# Ulimate.net
KiCad netlist of a schematic drawn in EAGLE
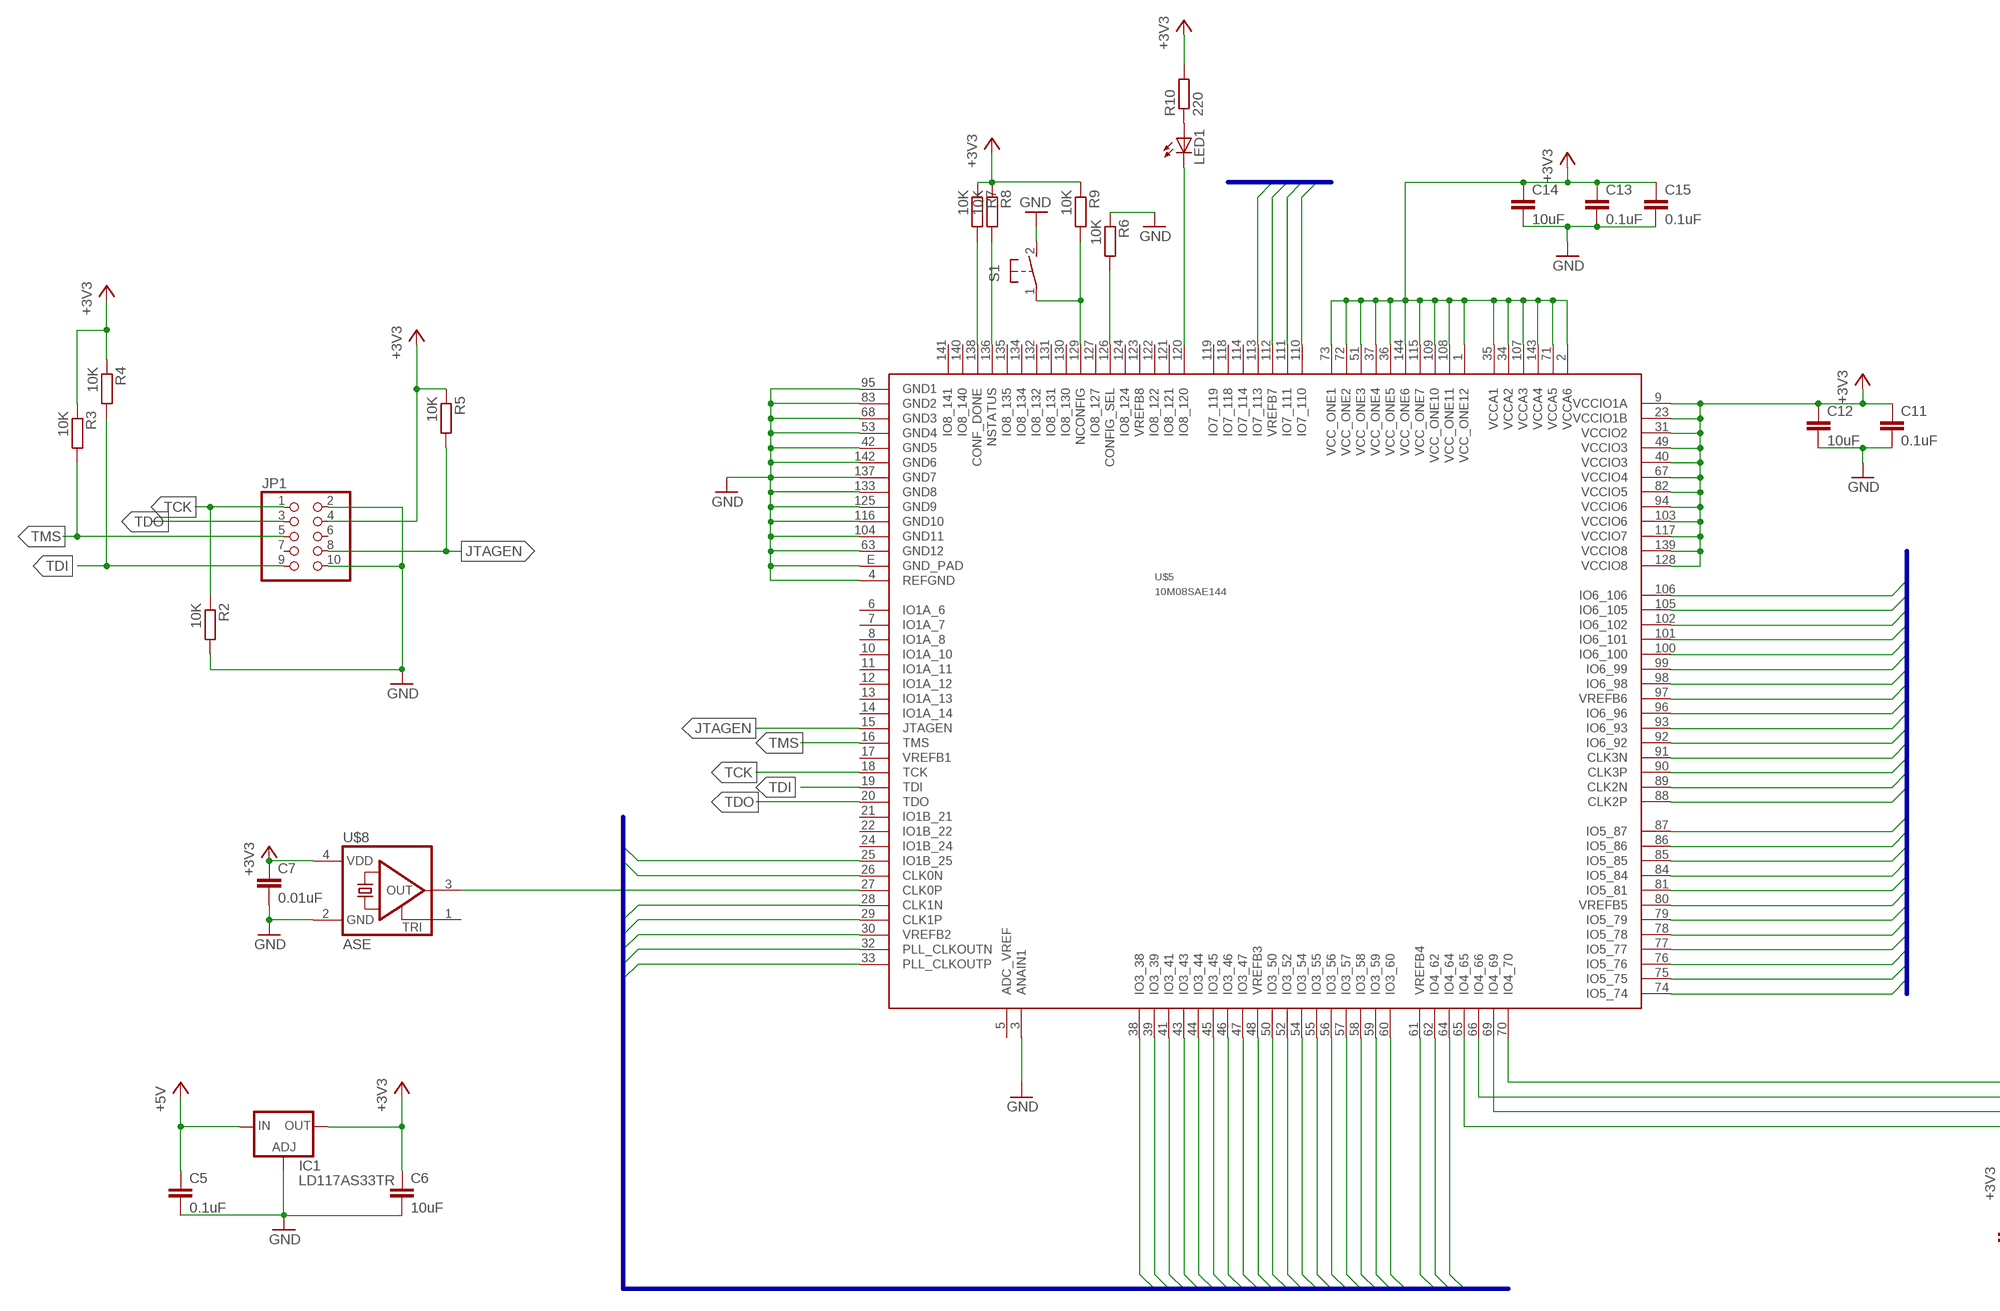
[diagram p0: schematic, sheet 1, part 1 of 2]
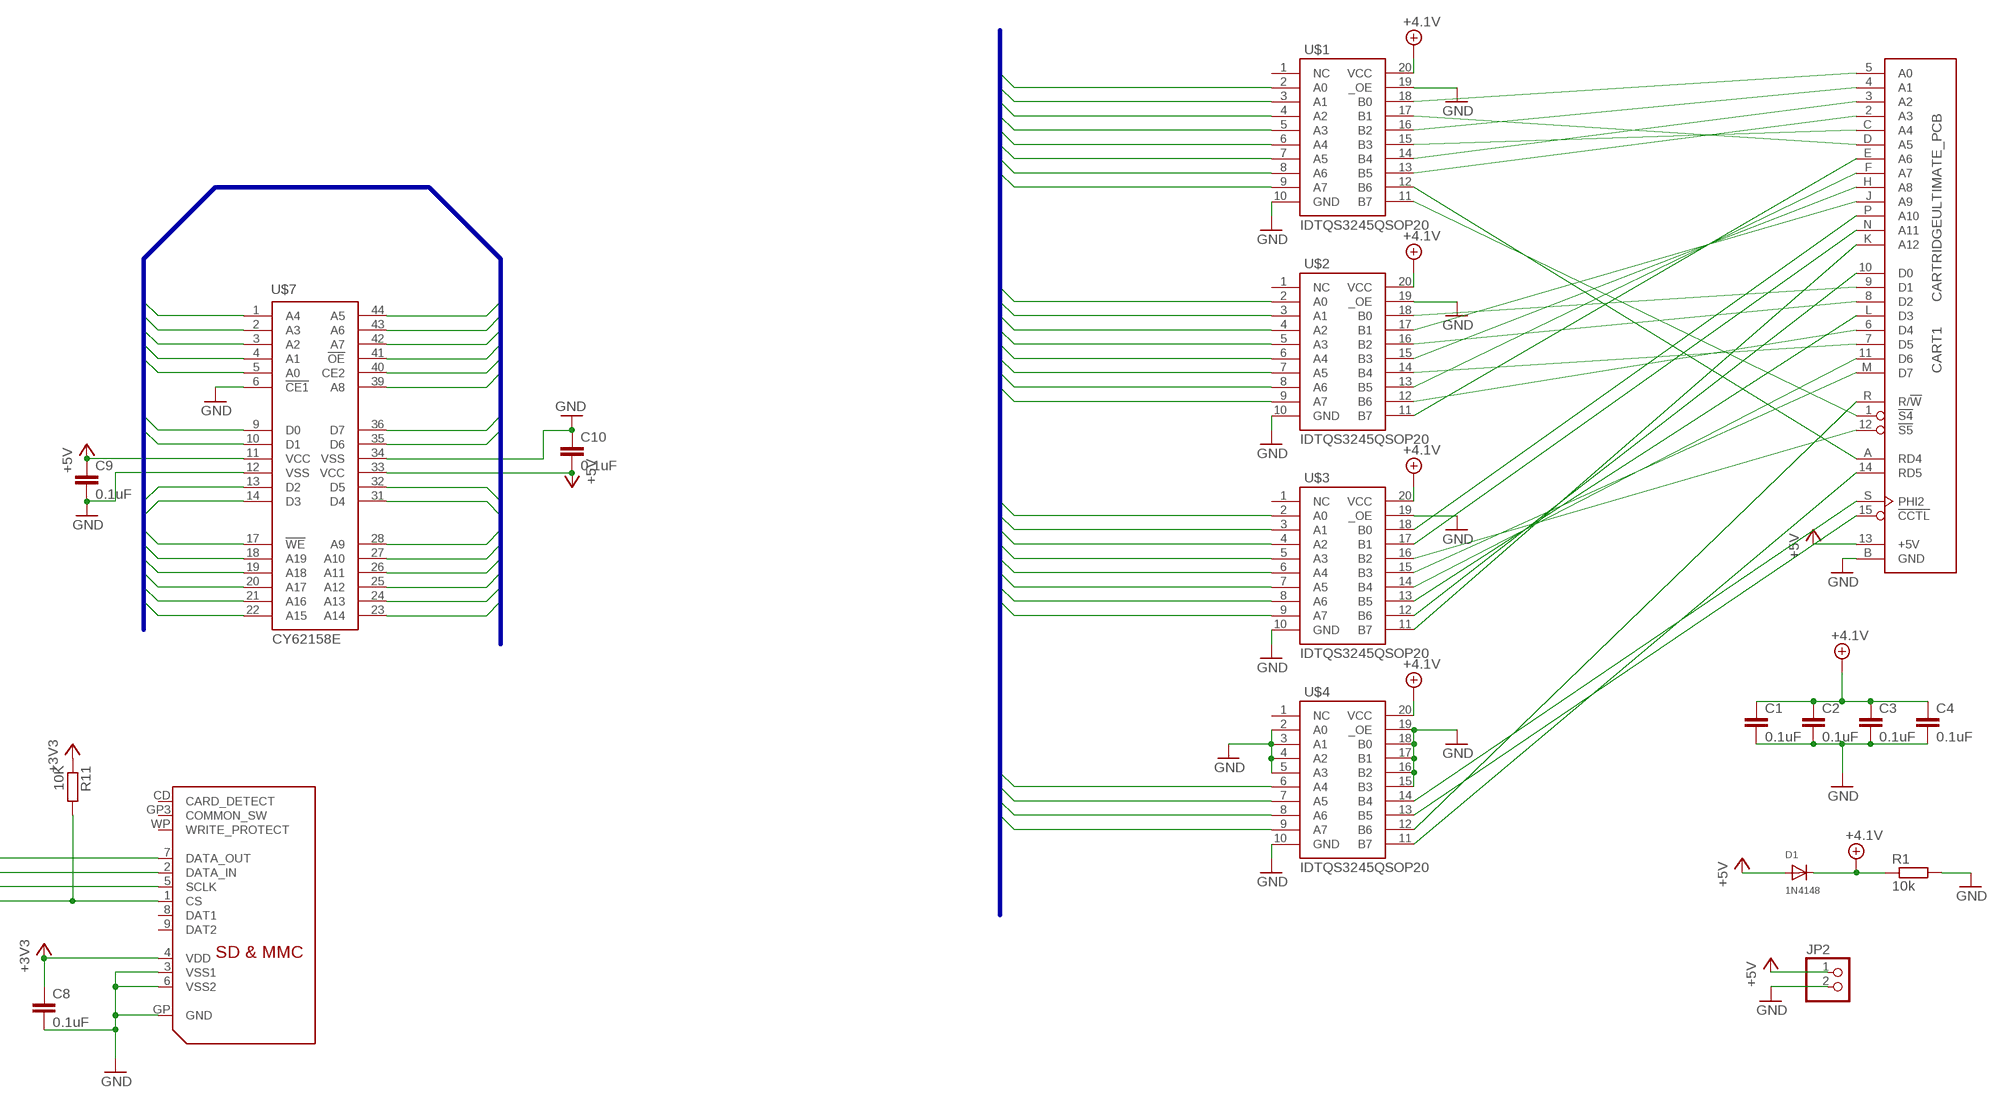
[diagram p1: schematic, sheet 1, part 2 of 2]

(export (version "E")
  (design (tool "Eeschema 10.0.6"))
  (components
    (comp (ref "C1")
      (value "0.1uF")
      (footprint "eagle-import:C0805K")
      (libsource (lib "eagle-import") (part "C-EUC0805K"))
    )
    (comp (ref "C2")
      (value "0.1uF")
      (footprint "eagle-import:C0805K")
      (libsource (lib "eagle-import") (part "C-EUC0805K"))
    )
    (comp (ref "C3")
      (value "0.1uF")
      (footprint "eagle-import:C0805K")
      (libsource (lib "eagle-import") (part "C-EUC0805K"))
    )
    (comp (ref "C4")
      (value "0.1uF")
      (footprint "eagle-import:C0805K")
      (libsource (lib "eagle-import") (part "C-EUC0805K"))
    )
    (comp (ref "C5")
      (value "0.1uF")
      (footprint "eagle-import:C0805K")
      (libsource (lib "eagle-import") (part "C-EUC0805K"))
    )
    (comp (ref "C6")
      (value "10uF")
      (footprint "eagle-import:C0805K")
      (libsource (lib "eagle-import") (part "C-EUC0805K"))
    )
    (comp (ref "C7")
      (value "0.01uF")
      (footprint "eagle-import:C0805K")
      (libsource (lib "eagle-import") (part "C-EUC0805K"))
    )
    (comp (ref "C8")
      (value "0.1uF")
      (footprint "eagle-import:C0805K")
      (libsource (lib "eagle-import") (part "C-EUC0805K"))
    )
    (comp (ref "C9")
      (value "0.1uF")
      (footprint "eagle-import:C0805K")
      (libsource (lib "eagle-import") (part "C-EUC0805K"))
    )
    (comp (ref "C10")
      (value "0.1uF")
      (footprint "eagle-import:C0805K")
      (libsource (lib "eagle-import") (part "C-EUC0805K"))
    )
    (comp (ref "C11")
      (value "0.1uF")
      (footprint "eagle-import:C0805K")
      (libsource (lib "eagle-import") (part "C-EUC0805K"))
    )
    (comp (ref "C12")
      (value "10uF")
      (footprint "eagle-import:C0805K")
      (libsource (lib "eagle-import") (part "C-EUC0805K"))
    )
    (comp (ref "C13")
      (value "0.1uF")
      (footprint "eagle-import:C0805K")
      (libsource (lib "eagle-import") (part "C-EUC0805K"))
    )
    (comp (ref "C14")
      (value "10uF")
      (footprint "eagle-import:C0805K")
      (libsource (lib "eagle-import") (part "C-EUC0805K"))
    )
    (comp (ref "C15")
      (value "0.1uF")
      (footprint "eagle-import:C0805K")
      (libsource (lib "eagle-import") (part "C-EUC0805K"))
    )
    (comp (ref "CART1")
      (value "CARTRIDGEULTIMATE_PCB")
      (footprint "eagle-import:CART_ULTIMATE")
      (libsource (lib "eagle-import") (part "CARTRIDGEULTIMATE_PCB"))
    )
    (comp (ref "D1")
      (value "1N4148")
      (footprint "eagle-import:SOD-123FL")
      (libsource (lib "eagle-import") (part "DIODE_SOD-123FL"))
    )
    (comp (ref "IC1")
      (value "LD117AS33TR")
      (footprint "eagle-import:SOT223")
      (libsource (lib "eagle-import") (part "LD117A?S33TR"))
    )
    (comp (ref "JP1")
      (value "PINHD-2X5")
      (footprint "eagle-import:2X05")
      (libsource (lib "eagle-import") (part "PINHD-2X5"))
    )
    (comp (ref "JP2")
      (value "PINHD-1X2")
      (footprint "eagle-import:1X02")
      (libsource (lib "eagle-import") (part "PINHD-1X2"))
    )
    (comp (ref "LED1")
      (value "LEDSML0805")
      (footprint "eagle-import:SML0805")
      (libsource (lib "eagle-import") (part "LEDSML0805"))
    )
    (comp (ref "R1")
      (value "10k")
      (footprint "eagle-import:R0805")
      (libsource (lib "eagle-import") (part "R-EU_R0805"))
    )
    (comp (ref "R2")
      (value "10K")
      (footprint "eagle-import:R0805")
      (libsource (lib "eagle-import") (part "R-EU_R0805"))
    )
    (comp (ref "R3")
      (value "10K")
      (footprint "eagle-import:R0805")
      (libsource (lib "eagle-import") (part "R-EU_R0805"))
    )
    (comp (ref "R4")
      (value "10K")
      (footprint "eagle-import:R0805")
      (libsource (lib "eagle-import") (part "R-EU_R0805"))
    )
    (comp (ref "R5")
      (value "10K")
      (footprint "eagle-import:R0805")
      (libsource (lib "eagle-import") (part "R-EU_R0805"))
    )
    (comp (ref "R6")
      (value "10K")
      (footprint "eagle-import:R0805")
      (libsource (lib "eagle-import") (part "R-EU_R0805"))
    )
    (comp (ref "R7")
      (value "10K")
      (footprint "eagle-import:R0805")
      (libsource (lib "eagle-import") (part "R-EU_R0805"))
    )
    (comp (ref "R8")
      (value "10K")
      (footprint "eagle-import:R0805")
      (libsource (lib "eagle-import") (part "R-EU_R0805"))
    )
    (comp (ref "R9")
      (value "10K")
      (footprint "eagle-import:R0805")
      (libsource (lib "eagle-import") (part "R-EU_R0805"))
    )
    (comp (ref "R10")
      (value "220")
      (footprint "eagle-import:R0805")
      (libsource (lib "eagle-import") (part "R-EU_R0805"))
    )
    (comp (ref "R11")
      (value "10K")
      (footprint "eagle-import:R0805")
      (libsource (lib "eagle-import") (part "R-EU_R0805"))
    )
    (comp (ref "S1")
      (value "31-XXSKINNY")
      (footprint "eagle-import:B3F-31XX-SKINNIER")
      (libsource (lib "eagle-import") (part "31-XXSKINNY"))
    )
    (comp (ref "U$1")
      (value "IDTQS3245QSOP20")
      (footprint "eagle-import:QSOP20")
      (libsource (lib "eagle-import") (part "IDTQS3245QSOP20"))
    )
    (comp (ref "U$2")
      (value "IDTQS3245QSOP20")
      (footprint "eagle-import:QSOP20")
      (libsource (lib "eagle-import") (part "IDTQS3245QSOP20"))
    )
    (comp (ref "U$3")
      (value "IDTQS3245QSOP20")
      (footprint "eagle-import:QSOP20")
      (libsource (lib "eagle-import") (part "IDTQS3245QSOP20"))
    )
    (comp (ref "U$4")
      (value "IDTQS3245QSOP20")
      (footprint "eagle-import:QSOP20")
      (libsource (lib "eagle-import") (part "IDTQS3245QSOP20"))
    )
    (comp (ref "U$5")
      (value "10M08SAE144")
      (footprint "eagle-import:EQFP144")
      (libsource (lib "eagle-import") (part "10M08SAE144"))
    )
    (comp (ref "U$6")
      (value "SDMMC06132")
      (footprint "eagle-import:06132")
      (libsource (lib "eagle-import") (part "SDMMC06132"))
    )
    (comp (ref "U$7")
      (value "CY62158E")
      (footprint "eagle-import:TSOP44-II")
      (libsource (lib "eagle-import") (part "CY62158E"))
    )
    (comp (ref "U$8")
      (value "ASE")
      (footprint "eagle-import:ASE")
      (libsource (lib "eagle-import") (part "ASE"))
    )
  )
  (nets
    (net (code "1") (name "+3V3") (class "Default")
      (node (ref "C11") (pin "1") (pinfunction "1_1") (pintype "passive"))
      (node (ref "C12") (pin "1") (pinfunction "1_1") (pintype "passive"))
      (node (ref "C13") (pin "1") (pinfunction "1_1") (pintype "passive"))
      (node (ref "C14") (pin "1") (pinfunction "1_1") (pintype "passive"))
      (node (ref "C15") (pin "1") (pinfunction "1_1") (pintype "passive"))
      (node (ref "C6") (pin "1") (pinfunction "1_1") (pintype "passive"))
      (node (ref "C7") (pin "1") (pinfunction "1_1") (pintype "passive"))
      (node (ref "C8") (pin "1") (pinfunction "1_1") (pintype "passive"))
      (node (ref "IC1") (pin "4") (pinfunction "OUT_4") (pintype "passive"))
      (node (ref "JP1") (pin "4") (pinfunction "4_4") (pintype "passive"))
      (node (ref "R10") (pin "2") (pinfunction "2_2") (pintype "passive"))
      (node (ref "R11") (pin "1") (pinfunction "1_1") (pintype "passive"))
      (node (ref "R3") (pin "1") (pinfunction "1_1") (pintype "passive"))
      (node (ref "R4") (pin "1") (pinfunction "1_1") (pintype "passive"))
      (node (ref "R5") (pin "1") (pinfunction "1_1") (pintype "passive"))
      (node (ref "R7") (pin "1") (pinfunction "1_1") (pintype "passive"))
      (node (ref "R8") (pin "1") (pinfunction "1_1") (pintype "passive"))
      (node (ref "R9") (pin "1") (pinfunction "1_1") (pintype "passive"))
      (node (ref "U$5") (pin "1") (pinfunction "VCC_ONE12_1") (pintype "bidirectional"))
      (node (ref "U$5") (pin "103") (pinfunction "VCCIO6_103") (pintype "bidirectional"))
      (node (ref "U$5") (pin "107") (pinfunction "VCCA3_107") (pintype "bidirectional"))
      (node (ref "U$5") (pin "108") (pinfunction "VCC_ONE11_108") (pintype "bidirectional"))
      (node (ref "U$5") (pin "109") (pinfunction "VCC_ONE10_109") (pintype "bidirectional"))
      (node (ref "U$5") (pin "115") (pinfunction "VCC_ONE7_115") (pintype "bidirectional"))
      (node (ref "U$5") (pin "117") (pinfunction "VCCIO7_117") (pintype "bidirectional"))
      (node (ref "U$5") (pin "128") (pinfunction "VCCIO8_128") (pintype "bidirectional"))
      (node (ref "U$5") (pin "139") (pinfunction "VCCIO8_139") (pintype "bidirectional"))
      (node (ref "U$5") (pin "143") (pinfunction "VCCA4_143") (pintype "bidirectional"))
      (node (ref "U$5") (pin "144") (pinfunction "VCC_ONE6_144") (pintype "bidirectional"))
      (node (ref "U$5") (pin "2") (pinfunction "VCCA6_2") (pintype "bidirectional"))
      (node (ref "U$5") (pin "23") (pinfunction "VCCIO1B_23") (pintype "bidirectional"))
      (node (ref "U$5") (pin "31") (pinfunction "VCCIO2_31") (pintype "bidirectional"))
      (node (ref "U$5") (pin "34") (pinfunction "VCCA2_34") (pintype "bidirectional"))
      (node (ref "U$5") (pin "35") (pinfunction "VCCA1_35") (pintype "bidirectional"))
      (node (ref "U$5") (pin "36") (pinfunction "VCC_ONE5_36") (pintype "bidirectional"))
      (node (ref "U$5") (pin "37") (pinfunction "VCC_ONE4_37") (pintype "bidirectional"))
      (node (ref "U$5") (pin "40") (pinfunction "VCCIO3_40") (pintype "bidirectional"))
      (node (ref "U$5") (pin "49") (pinfunction "VCCIO3_49") (pintype "bidirectional"))
      (node (ref "U$5") (pin "51") (pinfunction "VCC_ONE3_51") (pintype "bidirectional"))
      (node (ref "U$5") (pin "67") (pinfunction "VCCIO4_67") (pintype "bidirectional"))
      (node (ref "U$5") (pin "71") (pinfunction "VCCA5_71") (pintype "bidirectional"))
      (node (ref "U$5") (pin "72") (pinfunction "VCC_ONE2_72") (pintype "bidirectional"))
      (node (ref "U$5") (pin "73") (pinfunction "VCC_ONE1_73") (pintype "bidirectional"))
      (node (ref "U$5") (pin "82") (pinfunction "VCCIO5_82") (pintype "bidirectional"))
      (node (ref "U$5") (pin "9") (pinfunction "VCCIO1A_9") (pintype "bidirectional"))
      (node (ref "U$5") (pin "94") (pinfunction "VCCIO6_94") (pintype "bidirectional"))
      (node (ref "U$6") (pin "4") (pinfunction "VDD_4") (pintype "power_in"))
      (node (ref "U$8") (pin "4") (pinfunction "VDD_4") (pintype "power_in"))
    )
    (net (code "2") (name "+4.1V") (class "Default")
      (node (ref "C1") (pin "1") (pinfunction "1_1") (pintype "passive"))
      (node (ref "C2") (pin "1") (pinfunction "1_1") (pintype "passive"))
      (node (ref "C3") (pin "1") (pinfunction "1_1") (pintype "passive"))
      (node (ref "C4") (pin "1") (pinfunction "1_1") (pintype "passive"))
      (node (ref "D1") (pin "C") (pinfunction "C_C") (pintype "passive"))
      (node (ref "R1") (pin "1") (pinfunction "1_1") (pintype "passive"))
      (node (ref "U$1") (pin "20") (pinfunction "VCC_20") (pintype "power_in"))
      (node (ref "U$2") (pin "20") (pinfunction "VCC_20") (pintype "power_in"))
      (node (ref "U$3") (pin "20") (pinfunction "VCC_20") (pintype "power_in"))
      (node (ref "U$4") (pin "20") (pinfunction "VCC_20") (pintype "power_in"))
    )
    (net (code "3") (name "+5V") (class "Default")
      (node (ref "C10") (pin "2") (pinfunction "2_2") (pintype "passive"))
      (node (ref "C5") (pin "1") (pinfunction "1_1") (pintype "passive"))
      (node (ref "C9") (pin "1") (pinfunction "1_1") (pintype "passive"))
      (node (ref "CART1") (pin "13") (pinfunction "+5V_13") (pintype "power_in"))
      (node (ref "D1") (pin "A") (pinfunction "A_A") (pintype "passive"))
      (node (ref "IC1") (pin "3") (pinfunction "IN_3") (pintype "input"))
      (node (ref "JP2") (pin "1") (pinfunction "1_1") (pintype "passive"))
      (node (ref "U$7") (pin "11") (pinfunction "VCC_11") (pintype "bidirectional"))
      (node (ref "U$7") (pin "33") (pinfunction "VCC_33") (pintype "bidirectional"))
    )
    (net (code "4") (name "/A0") (class "Default")
      (node (ref "U$5") (pin "96") (pinfunction "IO6_96_96") (pintype "bidirectional"))
      (node (ref "U$7") (pin "5") (pinfunction "A0_5") (pintype "bidirectional"))
    )
    (net (code "5") (name "/A1") (class "Default")
      (node (ref "U$5") (pin "97") (pinfunction "VREFB6_97") (pintype "bidirectional"))
      (node (ref "U$7") (pin "4") (pinfunction "A1_4") (pintype "bidirectional"))
    )
    (net (code "6") (name "/A2") (class "Default")
      (node (ref "U$5") (pin "98") (pinfunction "IO6_98_98") (pintype "bidirectional"))
      (node (ref "U$7") (pin "3") (pinfunction "A2_3") (pintype "bidirectional"))
    )
    (net (code "7") (name "/A3") (class "Default")
      (node (ref "U$5") (pin "99") (pinfunction "IO6_99_99") (pintype "bidirectional"))
      (node (ref "U$7") (pin "2") (pinfunction "A3_2") (pintype "bidirectional"))
    )
    (net (code "8") (name "/A4") (class "Default")
      (node (ref "U$5") (pin "100") (pinfunction "IO6_100_100") (pintype "bidirectional"))
      (node (ref "U$7") (pin "1") (pinfunction "A4_1") (pintype "bidirectional"))
    )
    (net (code "9") (name "/A5") (class "Default")
      (node (ref "U$5") (pin "105") (pinfunction "IO6_105_105") (pintype "bidirectional"))
      (node (ref "U$7") (pin "44") (pinfunction "A5_44") (pintype "bidirectional"))
    )
    (net (code "10") (name "/A6") (class "Default")
      (node (ref "U$5") (pin "102") (pinfunction "IO6_102_102") (pintype "bidirectional"))
      (node (ref "U$7") (pin "43") (pinfunction "A6_43") (pintype "bidirectional"))
    )
    (net (code "11") (name "/A7") (class "Default")
      (node (ref "U$5") (pin "101") (pinfunction "IO6_101_101") (pintype "bidirectional"))
      (node (ref "U$7") (pin "42") (pinfunction "A7_42") (pintype "bidirectional"))
    )
    (net (code "12") (name "/A8") (class "Default")
      (node (ref "U$5") (pin "111") (pinfunction "IO7_111_111") (pintype "bidirectional"))
      (node (ref "U$7") (pin "39") (pinfunction "A8_39") (pintype "bidirectional"))
    )
    (net (code "13") (name "/A9") (class "Default")
      (node (ref "U$5") (pin "76") (pinfunction "IO5_76_76") (pintype "bidirectional"))
      (node (ref "U$7") (pin "28") (pinfunction "A9_28") (pintype "bidirectional"))
    )
    (net (code "14") (name "/A10") (class "Default")
      (node (ref "U$5") (pin "77") (pinfunction "IO5_77_77") (pintype "bidirectional"))
      (node (ref "U$7") (pin "27") (pinfunction "A10_27") (pintype "bidirectional"))
    )
    (net (code "15") (name "/A11") (class "Default")
      (node (ref "U$5") (pin "78") (pinfunction "IO5_78_78") (pintype "bidirectional"))
      (node (ref "U$7") (pin "26") (pinfunction "A11_26") (pintype "bidirectional"))
    )
    (net (code "16") (name "/A12") (class "Default")
      (node (ref "U$5") (pin "79") (pinfunction "IO5_79_79") (pintype "bidirectional"))
      (node (ref "U$7") (pin "25") (pinfunction "A12_25") (pintype "bidirectional"))
    )
    (net (code "17") (name "/A13") (class "Default")
      (node (ref "U$5") (pin "80") (pinfunction "VREFB5_80") (pintype "bidirectional"))
      (node (ref "U$7") (pin "24") (pinfunction "A13_24") (pintype "bidirectional"))
    )
    (net (code "18") (name "/A14") (class "Default")
      (node (ref "U$5") (pin "81") (pinfunction "IO5_81_81") (pintype "bidirectional"))
      (node (ref "U$7") (pin "23") (pinfunction "A14_23") (pintype "bidirectional"))
    )
    (net (code "19") (name "/A15") (class "Default")
      (node (ref "U$5") (pin "84") (pinfunction "IO5_84_84") (pintype "bidirectional"))
      (node (ref "U$7") (pin "22") (pinfunction "A15_22") (pintype "bidirectional"))
    )
    (net (code "20") (name "/A16") (class "Default")
      (node (ref "U$5") (pin "85") (pinfunction "IO5_85_85") (pintype "bidirectional"))
      (node (ref "U$7") (pin "21") (pinfunction "A16_21") (pintype "bidirectional"))
    )
    (net (code "21") (name "/A17") (class "Default")
      (node (ref "U$5") (pin "86") (pinfunction "IO5_86_86") (pintype "bidirectional"))
      (node (ref "U$7") (pin "20") (pinfunction "A17_20") (pintype "bidirectional"))
    )
    (net (code "22") (name "/A18") (class "Default")
      (node (ref "U$5") (pin "87") (pinfunction "IO5_87_87") (pintype "bidirectional"))
      (node (ref "U$7") (pin "19") (pinfunction "A18_19") (pintype "bidirectional"))
    )
    (net (code "23") (name "/A19") (class "Default")
      (node (ref "U$5") (pin "88") (pinfunction "CLK2P_88") (pintype "bidirectional"))
      (node (ref "U$7") (pin "18") (pinfunction "A19_18") (pintype "bidirectional"))
    )
    (net (code "24") (name "/CART_A0") (class "Default")
      (node (ref "U$1") (pin "2") (pinfunction "A0_2") (pintype "bidirectional"))
      (node (ref "U$5") (pin "39") (pinfunction "IO3_39_39") (pintype "bidirectional"))
    )
    (net (code "25") (name "/CART_A1") (class "Default")
      (node (ref "U$1") (pin "4") (pinfunction "A2_4") (pintype "bidirectional"))
      (node (ref "U$5") (pin "33") (pinfunction "PLL_CLKOUTP_33") (pintype "bidirectional"))
    )
    (net (code "26") (name "/CART_A2") (class "Default")
      (node (ref "U$1") (pin "6") (pinfunction "A4_6") (pintype "bidirectional"))
      (node (ref "U$5") (pin "30") (pinfunction "VREFB2_30") (pintype "bidirectional"))
    )
    (net (code "27") (name "/CART_A3") (class "Default")
      (node (ref "U$1") (pin "7") (pinfunction "A5_7") (pintype "bidirectional"))
      (node (ref "U$5") (pin "29") (pinfunction "CLK1P_29") (pintype "bidirectional"))
    )
    (net (code "28") (name "/CART_A4") (class "Default")
      (node (ref "U$1") (pin "5") (pinfunction "A3_5") (pintype "bidirectional"))
      (node (ref "U$5") (pin "32") (pinfunction "PLL_CLKOUTN_32") (pintype "bidirectional"))
    )
    (net (code "29") (name "/CART_A5") (class "Default")
      (node (ref "U$1") (pin "3") (pinfunction "A1_3") (pintype "bidirectional"))
      (node (ref "U$5") (pin "38") (pinfunction "IO3_38_38") (pintype "bidirectional"))
    )
    (net (code "30") (name "/CART_A6") (class "Default")
      (node (ref "U$2") (pin "9") (pinfunction "A7_9") (pintype "bidirectional"))
      (node (ref "U$5") (pin "41") (pinfunction "IO3_41_41") (pintype "bidirectional"))
    )
    (net (code "31") (name "/CART_A7") (class "Default")
      (node (ref "U$2") (pin "7") (pinfunction "A5_7") (pintype "bidirectional"))
      (node (ref "U$5") (pin "44") (pinfunction "IO3_44_44") (pintype "bidirectional"))
    )
    (net (code "32") (name "/CART_A8") (class "Default")
      (node (ref "U$2") (pin "5") (pinfunction "A3_5") (pintype "bidirectional"))
      (node (ref "U$5") (pin "46") (pinfunction "IO3_46_46") (pintype "bidirectional"))
    )
    (net (code "33") (name "/CART_A9") (class "Default")
      (node (ref "U$2") (pin "3") (pinfunction "A1_3") (pintype "bidirectional"))
      (node (ref "U$5") (pin "48") (pinfunction "VREFB3_48") (pintype "bidirectional"))
    )
    (net (code "34") (name "/CART_A10") (class "Default")
      (node (ref "U$3") (pin "2") (pinfunction "A0_2") (pintype "bidirectional"))
      (node (ref "U$5") (pin "60") (pinfunction "IO3_60_60") (pintype "bidirectional"))
    )
    (net (code "35") (name "/CART_A11") (class "Default")
      (node (ref "U$3") (pin "3") (pinfunction "A1_3") (pintype "bidirectional"))
      (node (ref "U$5") (pin "59") (pinfunction "IO3_59_59") (pintype "bidirectional"))
    )
    (net (code "36") (name "/CART_A12") (class "Default")
      (node (ref "U$3") (pin "9") (pinfunction "A7_9") (pintype "bidirectional"))
      (node (ref "U$5") (pin "52") (pinfunction "IO3_52_52") (pintype "bidirectional"))
    )
    (net (code "37") (name "/CART_CTL") (class "Default")
      (node (ref "U$4") (pin "7") (pinfunction "A5_7") (pintype "bidirectional"))
      (node (ref "U$5") (pin "64") (pinfunction "IO4_64_64") (pintype "bidirectional"))
    )
    (net (code "38") (name "/CART_D0") (class "Default")
      (node (ref "U$3") (pin "8") (pinfunction "A6_8") (pintype "bidirectional"))
      (node (ref "U$5") (pin "54") (pinfunction "IO3_54_54") (pintype "bidirectional"))
    )
    (net (code "39") (name "/CART_D1") (class "Default")
      (node (ref "U$2") (pin "2") (pinfunction "A0_2") (pintype "bidirectional"))
      (node (ref "U$5") (pin "50") (pinfunction "IO3_50_50") (pintype "bidirectional"))
    )
    (net (code "40") (name "/CART_D2") (class "Default")
      (node (ref "U$2") (pin "4") (pinfunction "A2_4") (pintype "bidirectional"))
      (node (ref "U$5") (pin "47") (pinfunction "IO3_47_47") (pintype "bidirectional"))
    )
    (net (code "41") (name "/CART_D3") (class "Default")
      (node (ref "U$3") (pin "7") (pinfunction "A5_7") (pintype "bidirectional"))
      (node (ref "U$5") (pin "55") (pinfunction "IO3_55_55") (pintype "bidirectional"))
    )
    (net (code "42") (name "/CART_D4") (class "Default")
      (node (ref "U$2") (pin "8") (pinfunction "A6_8") (pintype "bidirectional"))
      (node (ref "U$5") (pin "43") (pinfunction "IO3_43_43") (pintype "bidirectional"))
    )
    (net (code "43") (name "/CART_D5") (class "Default")
      (node (ref "U$2") (pin "6") (pinfunction "A4_6") (pintype "bidirectional"))
      (node (ref "U$5") (pin "45") (pinfunction "IO3_45_45") (pintype "bidirectional"))
    )
    (net (code "44") (name "/CART_D6") (class "Default")
      (node (ref "U$3") (pin "6") (pinfunction "A4_6") (pintype "bidirectional"))
      (node (ref "U$5") (pin "56") (pinfunction "IO3_56_56") (pintype "bidirectional"))
    )
    (net (code "45") (name "/CART_D7") (class "Default")
      (node (ref "U$3") (pin "5") (pinfunction "A3_5") (pintype "bidirectional"))
      (node (ref "U$5") (pin "57") (pinfunction "IO3_57_57") (pintype "bidirectional"))
    )
    (net (code "46") (name "/CART_PHI") (class "Default")
      (node (ref "U$4") (pin "6") (pinfunction "A4_6") (pintype "bidirectional"))
      (node (ref "U$5") (pin "26") (pinfunction "CLK0N_26") (pintype "bidirectional"))
    )
    (net (code "47") (name "/CART_RD4") (class "Default")
      (node (ref "U$1") (pin "8") (pinfunction "A6_8") (pintype "bidirectional"))
      (node (ref "U$5") (pin "25") (pinfunction "IO1B_25_25") (pintype "bidirectional"))
    )
    (net (code "48") (name "/CART_RD5") (class "Default")
      (node (ref "U$4") (pin "9") (pinfunction "A7_9") (pintype "bidirectional"))
      (node (ref "U$5") (pin "61") (pinfunction "VREFB4_61") (pintype "bidirectional"))
    )
    (net (code "49") (name "/CART_RW") (class "Default")
      (node (ref "U$4") (pin "8") (pinfunction "A6_8") (pintype "bidirectional"))
      (node (ref "U$5") (pin "62") (pinfunction "IO4_62_62") (pintype "bidirectional"))
    )
    (net (code "50") (name "/CART_S4") (class "Default")
      (node (ref "U$1") (pin "9") (pinfunction "A7_9") (pintype "bidirectional"))
      (node (ref "U$5") (pin "28") (pinfunction "CLK1N_28") (pintype "bidirectional"))
    )
    (net (code "51") (name "/CART_S5") (class "Default")
      (node (ref "U$3") (pin "4") (pinfunction "A2_4") (pintype "bidirectional"))
      (node (ref "U$5") (pin "58") (pinfunction "IO3_58_58") (pintype "bidirectional"))
    )
    (net (code "52") (name "/CE") (class "Default")
      (node (ref "U$5") (pin "110") (pinfunction "IO7_110_110") (pintype "bidirectional"))
      (node (ref "U$7") (pin "40") (pinfunction "CE2_40") (pintype "bidirectional"))
    )
    (net (code "53") (name "/D0") (class "Default")
      (node (ref "U$5") (pin "93") (pinfunction "IO6_93_93") (pintype "bidirectional"))
      (node (ref "U$7") (pin "9") (pinfunction "D0_9") (pintype "bidirectional"))
    )
    (net (code "54") (name "/D1") (class "Default")
      (node (ref "U$5") (pin "92") (pinfunction "IO6_92_92") (pintype "bidirectional"))
      (node (ref "U$7") (pin "10") (pinfunction "D1_10") (pintype "bidirectional"))
    )
    (net (code "55") (name "/D2") (class "Default")
      (node (ref "U$5") (pin "91") (pinfunction "CLK3N_91") (pintype "bidirectional"))
      (node (ref "U$7") (pin "13") (pinfunction "D2_13") (pintype "bidirectional"))
    )
    (net (code "56") (name "/D3") (class "Default")
      (node (ref "U$5") (pin "90") (pinfunction "CLK3P_90") (pintype "bidirectional"))
      (node (ref "U$7") (pin "14") (pinfunction "D3_14") (pintype "bidirectional"))
    )
    (net (code "57") (name "/D4") (class "Default")
      (node (ref "U$5") (pin "75") (pinfunction "IO5_75_75") (pintype "bidirectional"))
      (node (ref "U$7") (pin "31") (pinfunction "D4_31") (pintype "bidirectional"))
    )
    (net (code "58") (name "/D5") (class "Default")
      (node (ref "U$5") (pin "74") (pinfunction "IO5_74_74") (pintype "bidirectional"))
      (node (ref "U$7") (pin "32") (pinfunction "D5_32") (pintype "bidirectional"))
    )
    (net (code "59") (name "/D6") (class "Default")
      (node (ref "U$5") (pin "113") (pinfunction "IO7_113_113") (pintype "bidirectional"))
      (node (ref "U$7") (pin "35") (pinfunction "D6_35") (pintype "bidirectional"))
    )
    (net (code "60") (name "/D7") (class "Default")
      (node (ref "U$5") (pin "112") (pinfunction "VREFB7_112") (pintype "bidirectional"))
      (node (ref "U$7") (pin "36") (pinfunction "D7_36") (pintype "bidirectional"))
    )
    (net (code "63") (name "/~{OE}") (class "Default")
      (node (ref "U$5") (pin "106") (pinfunction "IO6_106_106") (pintype "bidirectional"))
      (node (ref "U$7") (pin "41") (pinfunction "~{OE}_41") (pintype "bidirectional"))
    )
    (net (code "64") (name "/~{WE}") (class "Default")
      (node (ref "U$5") (pin "89") (pinfunction "CLK2N_89") (pintype "bidirectional"))
      (node (ref "U$7") (pin "17") (pinfunction "~{WE}_17") (pintype "bidirectional"))
    )
    (net (code "65") (name "GND") (class "Default")
      (node (ref "C1") (pin "2") (pinfunction "2_2") (pintype "passive"))
      (node (ref "C10") (pin "1") (pinfunction "1_1") (pintype "passive"))
      (node (ref "C11") (pin "2") (pinfunction "2_2") (pintype "passive"))
      (node (ref "C12") (pin "2") (pinfunction "2_2") (pintype "passive"))
      (node (ref "C13") (pin "2") (pinfunction "2_2") (pintype "passive"))
      (node (ref "C14") (pin "2") (pinfunction "2_2") (pintype "passive"))
      (node (ref "C15") (pin "2") (pinfunction "2_2") (pintype "passive"))
      (node (ref "C2") (pin "2") (pinfunction "2_2") (pintype "passive"))
      (node (ref "C3") (pin "2") (pinfunction "2_2") (pintype "passive"))
      (node (ref "C4") (pin "2") (pinfunction "2_2") (pintype "passive"))
      (node (ref "C5") (pin "2") (pinfunction "2_2") (pintype "passive"))
      (node (ref "C6") (pin "2") (pinfunction "2_2") (pintype "passive"))
      (node (ref "C7") (pin "2") (pinfunction "2_2") (pintype "passive"))
      (node (ref "C8") (pin "2") (pinfunction "2_2") (pintype "passive"))
      (node (ref "C9") (pin "2") (pinfunction "2_2") (pintype "passive"))
      (node (ref "CART1") (pin "B") (pinfunction "GND_B") (pintype "power_in"))
      (node (ref "IC1") (pin "1") (pinfunction "ADJ_1") (pintype "input"))
      (node (ref "JP1") (pin "10") (pinfunction "10_10") (pintype "passive"))
      (node (ref "JP1") (pin "2") (pinfunction "2_2") (pintype "passive"))
      (node (ref "JP2") (pin "2") (pinfunction "2_2") (pintype "passive"))
      (node (ref "R1") (pin "2") (pinfunction "2_2") (pintype "passive"))
      (node (ref "R2") (pin "2") (pinfunction "2_2") (pintype "passive"))
      (node (ref "R6") (pin "1") (pinfunction "1_1") (pintype "passive"))
      (node (ref "S1") (pin "2") (pinfunction "S_2") (pintype "passive"))
      (node (ref "U$1") (pin "10") (pinfunction "GND_10") (pintype "power_in"))
      (node (ref "U$1") (pin "19") (pinfunction "_OE_19") (pintype "bidirectional"))
      (node (ref "U$2") (pin "10") (pinfunction "GND_10") (pintype "power_in"))
      (node (ref "U$2") (pin "19") (pinfunction "_OE_19") (pintype "bidirectional"))
      (node (ref "U$3") (pin "10") (pinfunction "GND_10") (pintype "power_in"))
      (node (ref "U$3") (pin "19") (pinfunction "_OE_19") (pintype "bidirectional"))
      (node (ref "U$4") (pin "10") (pinfunction "GND_10") (pintype "power_in"))
      (node (ref "U$4") (pin "15") (pinfunction "B3_15") (pintype "bidirectional"))
      (node (ref "U$4") (pin "16") (pinfunction "B2_16") (pintype "bidirectional"))
      (node (ref "U$4") (pin "17") (pinfunction "B1_17") (pintype "bidirectional"))
      (node (ref "U$4") (pin "18") (pinfunction "B0_18") (pintype "bidirectional"))
      (node (ref "U$4") (pin "19") (pinfunction "_OE_19") (pintype "bidirectional"))
      (node (ref "U$4") (pin "2") (pinfunction "A0_2") (pintype "bidirectional"))
      (node (ref "U$4") (pin "3") (pinfunction "A1_3") (pintype "bidirectional"))
      (node (ref "U$4") (pin "4") (pinfunction "A2_4") (pintype "bidirectional"))
      (node (ref "U$4") (pin "5") (pinfunction "A3_5") (pintype "bidirectional"))
      (node (ref "U$5") (pin "104") (pinfunction "GND11_104") (pintype "bidirectional"))
      (node (ref "U$5") (pin "116") (pinfunction "GND10_116") (pintype "bidirectional"))
      (node (ref "U$5") (pin "125") (pinfunction "GND9_125") (pintype "bidirectional"))
      (node (ref "U$5") (pin "133") (pinfunction "GND8_133") (pintype "bidirectional"))
      (node (ref "U$5") (pin "137") (pinfunction "GND7_137") (pintype "bidirectional"))
      (node (ref "U$5") (pin "142") (pinfunction "GND6_142") (pintype "bidirectional"))
      (node (ref "U$5") (pin "3") (pinfunction "ANAIN1_3") (pintype "bidirectional"))
      (node (ref "U$5") (pin "4") (pinfunction "REFGND_4") (pintype "bidirectional"))
      (node (ref "U$5") (pin "42") (pinfunction "GND5_42") (pintype "bidirectional"))
      (node (ref "U$5") (pin "53") (pinfunction "GND4_53") (pintype "bidirectional"))
      (node (ref "U$5") (pin "63") (pinfunction "GND12_63") (pintype "bidirectional"))
      (node (ref "U$5") (pin "68") (pinfunction "GND3_68") (pintype "bidirectional"))
      (node (ref "U$5") (pin "83") (pinfunction "GND2_83") (pintype "bidirectional"))
      (node (ref "U$5") (pin "95") (pinfunction "GND1_95") (pintype "bidirectional"))
      (node (ref "U$5") (pin "E") (pinfunction "GND_PAD_E") (pintype "bidirectional"))
      (node (ref "U$6") (pin "3") (pinfunction "VSS1_3") (pintype "power_in"))
      (node (ref "U$6") (pin "6") (pinfunction "VSS2_6") (pintype "power_in"))
      (node (ref "U$6") (pin "GP") (pinfunction "GND_GP") (pintype "power_in"))
      (node (ref "U$7") (pin "12") (pinfunction "VSS_12") (pintype "bidirectional"))
      (node (ref "U$7") (pin "34") (pinfunction "VSS_34") (pintype "bidirectional"))
      (node (ref "U$7") (pin "6") (pinfunction "~{CE1}_6") (pintype "bidirectional"))
      (node (ref "U$8") (pin "2") (pinfunction "GND_2") (pintype "power_in"))
    )
    (net (code "66") (name "JTAGEN") (class "Default")
      (node (ref "JP1") (pin "8") (pinfunction "8_8") (pintype "passive"))
      (node (ref "R5") (pin "2") (pinfunction "2_2") (pintype "passive"))
      (node (ref "U$5") (pin "15") (pinfunction "JTAGEN_15") (pintype "bidirectional"))
    )
    (net (code "67") (name "Net-(CART1-A0)") (class "Default")
      (node (ref "CART1") (pin "5") (pinfunction "A0_5") (pintype "output"))
      (node (ref "U$1") (pin "18") (pinfunction "B0_18") (pintype "bidirectional"))
    )
    (net (code "68") (name "Net-(CART1-A1)") (class "Default")
      (node (ref "CART1") (pin "4") (pinfunction "A1_4") (pintype "output"))
      (node (ref "U$1") (pin "16") (pinfunction "B2_16") (pintype "bidirectional"))
    )
    (net (code "69") (name "Net-(CART1-A2)") (class "Default")
      (node (ref "CART1") (pin "3") (pinfunction "A2_3") (pintype "output"))
      (node (ref "U$1") (pin "14") (pinfunction "B4_14") (pintype "bidirectional"))
    )
    (net (code "70") (name "Net-(CART1-A3)") (class "Default")
      (node (ref "CART1") (pin "2") (pinfunction "A3_2") (pintype "output"))
      (node (ref "U$1") (pin "13") (pinfunction "B5_13") (pintype "bidirectional"))
    )
    (net (code "71") (name "Net-(CART1-A4)") (class "Default")
      (node (ref "CART1") (pin "C") (pinfunction "A4_C") (pintype "output"))
      (node (ref "U$1") (pin "15") (pinfunction "B3_15") (pintype "bidirectional"))
    )
    (net (code "72") (name "Net-(CART1-A5)") (class "Default")
      (node (ref "CART1") (pin "D") (pinfunction "A5_D") (pintype "output"))
      (node (ref "U$1") (pin "17") (pinfunction "B1_17") (pintype "bidirectional"))
    )
    (net (code "73") (name "Net-(CART1-A6)") (class "Default")
      (node (ref "CART1") (pin "E") (pinfunction "A6_E") (pintype "output"))
      (node (ref "U$2") (pin "11") (pinfunction "B7_11") (pintype "bidirectional"))
    )
    (net (code "74") (name "Net-(CART1-A7)") (class "Default")
      (node (ref "CART1") (pin "F") (pinfunction "A7_F") (pintype "output"))
      (node (ref "U$2") (pin "13") (pinfunction "B5_13") (pintype "bidirectional"))
    )
    (net (code "75") (name "Net-(CART1-A8)") (class "Default")
      (node (ref "CART1") (pin "H") (pinfunction "A8_H") (pintype "output"))
      (node (ref "U$2") (pin "15") (pinfunction "B3_15") (pintype "bidirectional"))
    )
    (net (code "76") (name "Net-(CART1-A9)") (class "Default")
      (node (ref "CART1") (pin "J") (pinfunction "A9_J") (pintype "output"))
      (node (ref "U$2") (pin "17") (pinfunction "B1_17") (pintype "bidirectional"))
    )
    (net (code "77") (name "Net-(CART1-A10)") (class "Default")
      (node (ref "CART1") (pin "P") (pinfunction "A10_P") (pintype "output"))
      (node (ref "U$3") (pin "18") (pinfunction "B0_18") (pintype "bidirectional"))
    )
    (net (code "78") (name "Net-(CART1-A11)") (class "Default")
      (node (ref "CART1") (pin "N") (pinfunction "A11_N") (pintype "output"))
      (node (ref "U$3") (pin "17") (pinfunction "B1_17") (pintype "bidirectional"))
    )
    (net (code "79") (name "Net-(CART1-A12)") (class "Default")
      (node (ref "CART1") (pin "K") (pinfunction "A12_K") (pintype "output"))
      (node (ref "U$3") (pin "11") (pinfunction "B7_11") (pintype "bidirectional"))
    )
    (net (code "80") (name "Net-(CART1-D0)") (class "Default")
      (node (ref "CART1") (pin "10") (pinfunction "D0_10") (pintype "bidirectional"))
      (node (ref "U$3") (pin "12") (pinfunction "B6_12") (pintype "bidirectional"))
    )
    (net (code "81") (name "Net-(CART1-D1)") (class "Default")
      (node (ref "CART1") (pin "9") (pinfunction "D1_9") (pintype "bidirectional"))
      (node (ref "U$2") (pin "18") (pinfunction "B0_18") (pintype "bidirectional"))
    )
    (net (code "82") (name "Net-(CART1-D2)") (class "Default")
      (node (ref "CART1") (pin "8") (pinfunction "D2_8") (pintype "bidirectional"))
      (node (ref "U$2") (pin "16") (pinfunction "B2_16") (pintype "bidirectional"))
    )
    (net (code "83") (name "Net-(CART1-D3)") (class "Default")
      (node (ref "CART1") (pin "L") (pinfunction "D3_L") (pintype "bidirectional"))
      (node (ref "U$3") (pin "13") (pinfunction "B5_13") (pintype "bidirectional"))
    )
    (net (code "84") (name "Net-(CART1-D4)") (class "Default")
      (node (ref "CART1") (pin "6") (pinfunction "D4_6") (pintype "bidirectional"))
      (node (ref "U$2") (pin "12") (pinfunction "B6_12") (pintype "bidirectional"))
    )
    (net (code "85") (name "Net-(CART1-D5)") (class "Default")
      (node (ref "CART1") (pin "7") (pinfunction "D5_7") (pintype "bidirectional"))
      (node (ref "U$2") (pin "14") (pinfunction "B4_14") (pintype "bidirectional"))
    )
    (net (code "86") (name "Net-(CART1-D6)") (class "Default")
      (node (ref "CART1") (pin "11") (pinfunction "D6_11") (pintype "bidirectional"))
      (node (ref "U$3") (pin "14") (pinfunction "B4_14") (pintype "bidirectional"))
    )
    (net (code "87") (name "Net-(CART1-D7)") (class "Default")
      (node (ref "CART1") (pin "M") (pinfunction "D7_M") (pintype "bidirectional"))
      (node (ref "U$3") (pin "15") (pinfunction "B3_15") (pintype "bidirectional"))
    )
    (net (code "88") (name "Net-(CART1-PHI2)") (class "Default")
      (node (ref "CART1") (pin "S") (pinfunction "PHI2_S") (pintype "output"))
      (node (ref "U$4") (pin "14") (pinfunction "B4_14") (pintype "bidirectional"))
    )
    (net (code "89") (name "Net-(CART1-RD4)") (class "Default")
      (node (ref "CART1") (pin "A") (pinfunction "RD4_A") (pintype "input"))
      (node (ref "U$1") (pin "12") (pinfunction "B6_12") (pintype "bidirectional"))
    )
    (net (code "90") (name "Net-(CART1-RD5)") (class "Default")
      (node (ref "CART1") (pin "14") (pinfunction "RD5_14") (pintype "input"))
      (node (ref "U$4") (pin "11") (pinfunction "B7_11") (pintype "bidirectional"))
    )
    (net (code "91") (name "Net-(CART1-R{slash}~{W})") (class "Default")
      (node (ref "CART1") (pin "R") (pinfunction "R/~{W}_R") (pintype "output"))
      (node (ref "U$4") (pin "12") (pinfunction "B6_12") (pintype "bidirectional"))
    )
    (net (code "92") (name "Net-(CART1-~{CCTL})") (class "Default")
      (node (ref "CART1") (pin "15") (pinfunction "~{CCTL}_15") (pintype "output"))
      (node (ref "U$4") (pin "13") (pinfunction "B5_13") (pintype "bidirectional"))
    )
    (net (code "93") (name "Net-(CART1-~{S4})") (class "Default")
      (node (ref "CART1") (pin "1") (pinfunction "~{S4}_1") (pintype "output"))
      (node (ref "U$1") (pin "11") (pinfunction "B7_11") (pintype "bidirectional"))
    )
    (net (code "94") (name "Net-(CART1-~{S5})") (class "Default")
      (node (ref "CART1") (pin "12") (pinfunction "~{S5}_12") (pintype "output"))
      (node (ref "U$3") (pin "16") (pinfunction "B2_16") (pintype "bidirectional"))
    )
    (net (code "95") (name "Net-(LED1-PadA)") (class "Default")
      (node (ref "LED1") (pin "A") (pinfunction "A_A") (pintype "passive"))
      (node (ref "R10") (pin "1") (pinfunction "1_1") (pintype "passive"))
    )
    (net (code "96") (name "Net-(S1-P)") (class "Default")
      (node (ref "R9") (pin "2") (pinfunction "2_2") (pintype "passive"))
      (node (ref "S1") (pin "1") (pinfunction "P_1") (pintype "passive"))
      (node (ref "U$5") (pin "129") (pinfunction "NCONFIG_129") (pintype "bidirectional"))
    )
    (net (code "97") (name "Net-(U$5-CLK0P)") (class "Default")
      (node (ref "U$5") (pin "27") (pinfunction "CLK0P_27") (pintype "bidirectional"))
      (node (ref "U$8") (pin "3") (pinfunction "OUT_3") (pintype "output"))
    )
    (net (code "98") (name "Net-(U$5-CONFIG_SEL)") (class "Default")
      (node (ref "R6") (pin "2") (pinfunction "2_2") (pintype "passive"))
      (node (ref "U$5") (pin "126") (pinfunction "CONFIG_SEL_126") (pintype "bidirectional"))
    )
    (net (code "99") (name "Net-(U$5-CONF_DONE)") (class "Default")
      (node (ref "R7") (pin "2") (pinfunction "2_2") (pintype "passive"))
      (node (ref "U$5") (pin "138") (pinfunction "CONF_DONE_138") (pintype "bidirectional"))
    )
    (net (code "100") (name "Net-(U$5-IO4_65)") (class "Default")
      (node (ref "R11") (pin "2") (pinfunction "2_2") (pintype "passive"))
      (node (ref "U$5") (pin "65") (pinfunction "IO4_65_65") (pintype "bidirectional"))
      (node (ref "U$6") (pin "1") (pinfunction "CS_1") (pintype "input"))
    )
    (net (code "101") (name "Net-(U$5-IO4_66)") (class "Default")
      (node (ref "U$5") (pin "66") (pinfunction "IO4_66_66") (pintype "bidirectional"))
      (node (ref "U$6") (pin "2") (pinfunction "DATA_IN_2") (pintype "input"))
    )
    (net (code "102") (name "Net-(U$5-IO4_69)") (class "Default")
      (node (ref "U$5") (pin "69") (pinfunction "IO4_69_69") (pintype "bidirectional"))
      (node (ref "U$6") (pin "5") (pinfunction "SCLK_5") (pintype "input"))
    )
    (net (code "103") (name "Net-(U$5-IO4_70)") (class "Default")
      (node (ref "U$5") (pin "70") (pinfunction "IO4_70_70") (pintype "bidirectional"))
      (node (ref "U$6") (pin "7") (pinfunction "DATA_OUT_7") (pintype "output"))
    )
    (net (code "104") (name "Net-(U$5-IO8_120)") (class "Default")
      (node (ref "LED1") (pin "C") (pinfunction "C_C") (pintype "passive"))
      (node (ref "U$5") (pin "120") (pinfunction "IO8_120_120") (pintype "bidirectional"))
    )
    (net (code "105") (name "Net-(U$5-NSTATUS)") (class "Default")
      (node (ref "R8") (pin "2") (pinfunction "2_2") (pintype "passive"))
      (node (ref "U$5") (pin "136") (pinfunction "NSTATUS_136") (pintype "bidirectional"))
    )
    (net (code "106") (name "TCK") (class "Default")
      (node (ref "JP1") (pin "1") (pinfunction "1_1") (pintype "passive"))
      (node (ref "R2") (pin "1") (pinfunction "1_1") (pintype "passive"))
      (node (ref "U$5") (pin "18") (pinfunction "TCK_18") (pintype "bidirectional"))
    )
    (net (code "107") (name "TDI") (class "Default")
      (node (ref "JP1") (pin "9") (pinfunction "9_9") (pintype "passive"))
      (node (ref "R4") (pin "2") (pinfunction "2_2") (pintype "passive"))
      (node (ref "U$5") (pin "19") (pinfunction "TDI_19") (pintype "bidirectional"))
    )
    (net (code "108") (name "TDO") (class "Default")
      (node (ref "JP1") (pin "3") (pinfunction "3_3") (pintype "passive"))
      (node (ref "U$5") (pin "20") (pinfunction "TDO_20") (pintype "bidirectional"))
    )
    (net (code "109") (name "TMS") (class "Default")
      (node (ref "JP1") (pin "5") (pinfunction "5_5") (pintype "passive"))
      (node (ref "R3") (pin "2") (pinfunction "2_2") (pintype "passive"))
      (node (ref "U$5") (pin "16") (pinfunction "TMS_16") (pintype "bidirectional"))
    )
    (net (code "110") (name "unconnected-(JP1-Pad6)") (class "Default")
      (node (ref "JP1") (pin "6") (pinfunction "6_6") (pintype "passive"))
    )
    (net (code "111") (name "unconnected-(JP1-Pad7)") (class "Default")
      (node (ref "JP1") (pin "7") (pinfunction "7_7") (pintype "passive"))
    )
    (net (code "112") (name "unconnected-(U$1-NC-Pad1)") (class "Default")
      (node (ref "U$1") (pin "1") (pinfunction "NC_1") (pintype "no_connect"))
    )
    (net (code "113") (name "unconnected-(U$2-NC-Pad1)") (class "Default")
      (node (ref "U$2") (pin "1") (pinfunction "NC_1") (pintype "no_connect"))
    )
    (net (code "114") (name "unconnected-(U$3-NC-Pad1)") (class "Default")
      (node (ref "U$3") (pin "1") (pinfunction "NC_1") (pintype "no_connect"))
    )
    (net (code "115") (name "unconnected-(U$4-NC-Pad1)") (class "Default")
      (node (ref "U$4") (pin "1") (pinfunction "NC_1") (pintype "no_connect"))
    )
    (net (code "116") (name "unconnected-(U$5-ADC_VREF-Pad5)") (class "Default")
      (node (ref "U$5") (pin "5") (pinfunction "ADC_VREF_5") (pintype "bidirectional"))
    )
    (net (code "117") (name "unconnected-(U$5-IO1A_6-Pad6)") (class "Default")
      (node (ref "U$5") (pin "6") (pinfunction "IO1A_6_6") (pintype "bidirectional"))
    )
    (net (code "118") (name "unconnected-(U$5-IO1A_7-Pad7)") (class "Default")
      (node (ref "U$5") (pin "7") (pinfunction "IO1A_7_7") (pintype "bidirectional"))
    )
    (net (code "119") (name "unconnected-(U$5-IO1A_8-Pad8)") (class "Default")
      (node (ref "U$5") (pin "8") (pinfunction "IO1A_8_8") (pintype "bidirectional"))
    )
    (net (code "120") (name "unconnected-(U$5-IO1A_10-Pad10)") (class "Default")
      (node (ref "U$5") (pin "10") (pinfunction "IO1A_10_10") (pintype "bidirectional"))
    )
    (net (code "121") (name "unconnected-(U$5-IO1A_11-Pad11)") (class "Default")
      (node (ref "U$5") (pin "11") (pinfunction "IO1A_11_11") (pintype "bidirectional"))
    )
    (net (code "122") (name "unconnected-(U$5-IO1A_12-Pad12)") (class "Default")
      (node (ref "U$5") (pin "12") (pinfunction "IO1A_12_12") (pintype "bidirectional"))
    )
    (net (code "123") (name "unconnected-(U$5-IO1A_13-Pad13)") (class "Default")
      (node (ref "U$5") (pin "13") (pinfunction "IO1A_13_13") (pintype "bidirectional"))
    )
    (net (code "124") (name "unconnected-(U$5-IO1A_14-Pad14)") (class "Default")
      (node (ref "U$5") (pin "14") (pinfunction "IO1A_14_14") (pintype "bidirectional"))
    )
    (net (code "125") (name "unconnected-(U$5-IO1B_21-Pad21)") (class "Default")
      (node (ref "U$5") (pin "21") (pinfunction "IO1B_21_21") (pintype "bidirectional"))
    )
    (net (code "126") (name "unconnected-(U$5-IO1B_22-Pad22)") (class "Default")
      (node (ref "U$5") (pin "22") (pinfunction "IO1B_22_22") (pintype "bidirectional"))
    )
    (net (code "127") (name "unconnected-(U$5-IO1B_24-Pad24)") (class "Default")
      (node (ref "U$5") (pin "24") (pinfunction "IO1B_24_24") (pintype "bidirectional"))
    )
    (net (code "128") (name "unconnected-(U$5-IO7_114-Pad114)") (class "Default")
      (node (ref "U$5") (pin "114") (pinfunction "IO7_114_114") (pintype "bidirectional"))
    )
    (net (code "129") (name "unconnected-(U$5-IO7_118-Pad118)") (class "Default")
      (node (ref "U$5") (pin "118") (pinfunction "IO7_118_118") (pintype "bidirectional"))
    )
    (net (code "130") (name "unconnected-(U$5-IO7_119-Pad119)") (class "Default")
      (node (ref "U$5") (pin "119") (pinfunction "IO7_119_119") (pintype "bidirectional"))
    )
    (net (code "131") (name "unconnected-(U$5-IO8_121-Pad121)") (class "Default")
      (node (ref "U$5") (pin "121") (pinfunction "IO8_121_121") (pintype "bidirectional"))
    )
    (net (code "132") (name "unconnected-(U$5-IO8_122-Pad122)") (class "Default")
      (node (ref "U$5") (pin "122") (pinfunction "IO8_122_122") (pintype "bidirectional"))
    )
    (net (code "133") (name "unconnected-(U$5-IO8_124-Pad124)") (class "Default")
      (node (ref "U$5") (pin "124") (pinfunction "IO8_124_124") (pintype "bidirectional"))
    )
    (net (code "134") (name "unconnected-(U$5-IO8_127-Pad127)") (class "Default")
      (node (ref "U$5") (pin "127") (pinfunction "IO8_127_127") (pintype "bidirectional"))
    )
    (net (code "135") (name "unconnected-(U$5-IO8_130-Pad130)") (class "Default")
      (node (ref "U$5") (pin "130") (pinfunction "IO8_130_130") (pintype "bidirectional"))
    )
    (net (code "136") (name "unconnected-(U$5-IO8_131-Pad131)") (class "Default")
      (node (ref "U$5") (pin "131") (pinfunction "IO8_131_131") (pintype "bidirectional"))
    )
    (net (code "137") (name "unconnected-(U$5-IO8_132-Pad132)") (class "Default")
      (node (ref "U$5") (pin "132") (pinfunction "IO8_132_132") (pintype "bidirectional"))
    )
    (net (code "138") (name "unconnected-(U$5-IO8_134-Pad134)") (class "Default")
      (node (ref "U$5") (pin "134") (pinfunction "IO8_134_134") (pintype "bidirectional"))
    )
    (net (code "139") (name "unconnected-(U$5-IO8_135-Pad135)") (class "Default")
      (node (ref "U$5") (pin "135") (pinfunction "IO8_135_135") (pintype "bidirectional"))
    )
    (net (code "140") (name "unconnected-(U$5-IO8_140-Pad140)") (class "Default")
      (node (ref "U$5") (pin "140") (pinfunction "IO8_140_140") (pintype "bidirectional"))
    )
    (net (code "141") (name "unconnected-(U$5-IO8_141-Pad141)") (class "Default")
      (node (ref "U$5") (pin "141") (pinfunction "IO8_141_141") (pintype "bidirectional"))
    )
    (net (code "142") (name "unconnected-(U$5-VREFB1-Pad17)") (class "Default")
      (node (ref "U$5") (pin "17") (pinfunction "VREFB1_17") (pintype "bidirectional"))
    )
    (net (code "143") (name "unconnected-(U$5-VREFB8-Pad123)") (class "Default")
      (node (ref "U$5") (pin "123") (pinfunction "VREFB8_123") (pintype "bidirectional"))
    )
    (net (code "144") (name "unconnected-(U$6-CARD_DETECT-PadCD)") (class "Default")
      (node (ref "U$6") (pin "CD") (pinfunction "CARD_DETECT_CD") (pintype "passive"))
    )
    (net (code "145") (name "unconnected-(U$6-COMMON_SW-PadGP3)") (class "Default")
      (node (ref "U$6") (pin "GP3") (pinfunction "COMMON_SW_GP3") (pintype "passive"))
    )
    (net (code "146") (name "unconnected-(U$6-DAT1-Pad8)") (class "Default")
      (node (ref "U$6") (pin "8") (pinfunction "DAT1_8") (pintype "bidirectional"))
    )
    (net (code "147") (name "unconnected-(U$6-DAT2-Pad9)") (class "Default")
      (node (ref "U$6") (pin "9") (pinfunction "DAT2_9") (pintype "bidirectional"))
    )
    (net (code "148") (name "unconnected-(U$6-WRITE_PROTECT-PadWP)") (class "Default")
      (node (ref "U$6") (pin "WP") (pinfunction "WRITE_PROTECT_WP") (pintype "passive"))
    )
    (net (code "149") (name "unconnected-(U$8-TRI-Pad1)") (class "Default")
      (node (ref "U$8") (pin "1") (pinfunction "TRI_1") (pintype "input"))
    )
  )
)
